# CanController.net
KiCad netlist of a schematic drawn in Altium Designer
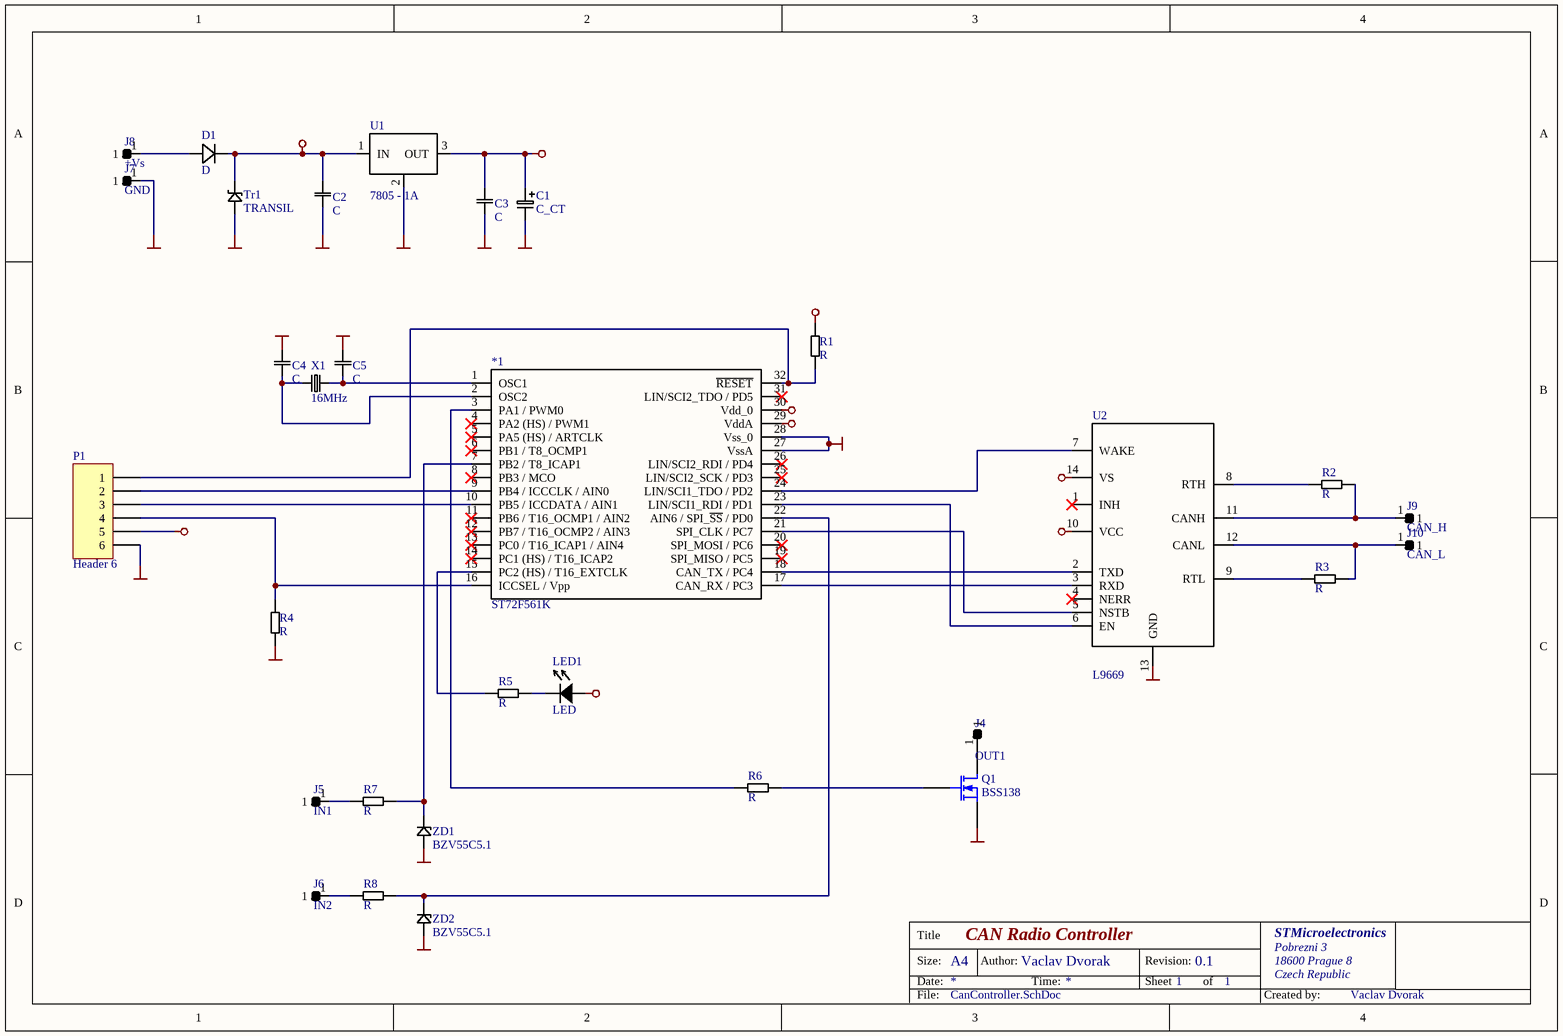
[diagram p0: CanController.SchDoc]

(export (version "E")
  (design (tool "Eeschema 10.0.6"))
  (components
    (comp (ref "*1")
      (value "ST72F561K")
      (footprint "QFP32")
      (libsource (lib "ABU_standard") (part "ST72F561K"))
    )
    (comp (ref "C1") (value "C_CT") (footprint "CTS A") (libsource (lib "ABU_standard") (part "C_CT")))
    (comp (ref "C2") (value "C") (footprint "C0805") (libsource (lib "ABU_standard") (part "C")))
    (comp (ref "C3") (value "C") (footprint "C0805") (libsource (lib "ABU_standard") (part "C")))
    (comp (ref "C4") (value "C") (footprint "C0805") (libsource (lib "ABU_standard") (part "C")))
    (comp (ref "C5") (value "C") (footprint "C0805") (libsource (lib "ABU_standard") (part "C")))
    (comp (ref "D1") (value "D") (footprint "SMA") (libsource (lib "ABU_STANDARD") (part "D")))
    (comp (ref "J4") (value "OUT1") (footprint "PIN") (libsource (lib "") (part "PIN_2")))
    (comp (ref "J5") (value "IN1") (footprint "PIN") (libsource (lib "ABU_standard") (part "PIN")))
    (comp (ref "J6") (value "IN2") (footprint "PIN") (libsource (lib "ABU_standard") (part "PIN")))
    (comp (ref "J7") (value "GND") (footprint "PIN") (libsource (lib "ABU_standard") (part "PIN")))
    (comp (ref "J8") (value "+Vs") (footprint "PIN") (libsource (lib "ABU_standard") (part "PIN")))
    (comp (ref "J9") (value "CAN_H") (footprint "PIN") (libsource (lib "") (part "PIN_1")))
    (comp (ref "J10") (value "CAN_L") (footprint "PIN") (libsource (lib "") (part "PIN_1")))
    (comp (ref "LED1") (value "LED") (footprint "LED_SMD") (libsource (lib "ABU_standard") (part "LED")))
    (comp (ref "P1")
      (value "Header 6")
      (footprint "HDR1X6")
      (description "Header, 6-Pin")
      (fields (field (name "PUBLISHER") "Altium Limited"))
      (libsource (lib "Miscellaneous Connectors") (part "Header 6"))
    )
    (comp (ref "Q1")
      (value "BSS138")
      (footprint "SOT23")
      (description "N-Channel Enhancement Mode Vertical DMOS FET")
      (fields (field (name "PUBLISHER") "Altium Limited"))
      (libsource (lib "ABU_standard") (part "BSS138"))
    )
    (comp (ref "R1") (value "R") (footprint "R0805") (libsource (lib "") (part "R_3")))
    (comp (ref "R2") (value "R") (footprint "R0805") (libsource (lib "") (part "R_2")))
    (comp (ref "R3") (value "R") (footprint "R0805") (libsource (lib "") (part "R_2")))
    (comp (ref "R4") (value "R") (footprint "R0805") (libsource (lib "") (part "R_1")))
    (comp (ref "R5") (value "R") (footprint "R0805") (libsource (lib "") (part "R_2")))
    (comp (ref "R6") (value "R") (footprint "R0805") (libsource (lib "ABU_standard") (part "R")))
    (comp (ref "R7") (value "R") (footprint "R0805") (libsource (lib "ABU_standard") (part "R")))
    (comp (ref "R8") (value "R") (footprint "R0805") (libsource (lib "ABU_standard") (part "R")))
    (comp (ref "Tr1") (value "TRANSIL") (footprint "SMAJ") (libsource (lib "ABU_STANDARD") (part "TRANSIL")))
    (comp (ref "U1")
      (value "7805 - 1A")
      (footprint "SOT-89")
      (libsource (lib "ABU_standard") (part "7805 - 1A"))
    )
    (comp (ref "U2")
      (value "L9669")
      (footprint "SO14")
      (libsource (lib "ABU_Door_module_project") (part "L9669"))
    )
    (comp (ref "X1") (value "16MHz") (footprint "HC-49U") (libsource (lib "ABU_standard") (part "XTALL")))
    (comp (ref "ZD1") (value "BZV55C5.1") (footprint "SOD80") (libsource (lib "ABU_standard") (part "ZD")))
    (comp (ref "ZD2") (value "BZV55C5.1") (footprint "SOD80") (libsource (lib "ABU_standard") (part "ZD")))
  )
  (nets
    (net (code "1") (name "+5V") (class "Default")
      (node (ref "*1") (pin "29") (pinfunction "VddA_29") (pintype "passive"))
      (node (ref "*1") (pin "30") (pinfunction "Vdd_0_30") (pintype "passive"))
      (node (ref "C1") (pin "1") (pinfunction "1_1") (pintype "passive"))
      (node (ref "C3") (pin "2") (pinfunction "2_2") (pintype "passive"))
      (node (ref "LED1") (pin "1") (pinfunction "A_1") (pintype "passive"))
      (node (ref "P1") (pin "5") (pinfunction "5_5") (pintype "passive"))
      (node (ref "R1") (pin "2") (pinfunction "2_2") (pintype "passive"))
      (node (ref "U1") (pin "3") (pinfunction "OUT_3") (pintype "passive"))
      (node (ref "U2") (pin "10") (pinfunction "VCC_10") (pintype "passive"))
    )
    (net (code "2") (name "GND") (class "Default")
      (node (ref "*1") (pin "27") (pinfunction "VssA_27") (pintype "passive"))
      (node (ref "*1") (pin "28") (pinfunction "Vss_0_28") (pintype "passive"))
      (node (ref "C1") (pin "2") (pinfunction "2_2") (pintype "passive"))
      (node (ref "C2") (pin "1") (pinfunction "1_1") (pintype "passive"))
      (node (ref "C3") (pin "1") (pinfunction "1_1") (pintype "passive"))
      (node (ref "C4") (pin "2") (pinfunction "2_2") (pintype "passive"))
      (node (ref "C5") (pin "2") (pinfunction "2_2") (pintype "passive"))
      (node (ref "J7") (pin "1") (pinfunction "1_1") (pintype "passive"))
      (node (ref "P1") (pin "6") (pinfunction "6_6") (pintype "passive"))
      (node (ref "Q1") (pin "2") (pinfunction "S_2") (pintype "passive"))
      (node (ref "R4") (pin "2") (pinfunction "2_2") (pintype "passive"))
      (node (ref "Tr1") (pin "1") (pinfunction "A_1") (pintype "passive"))
      (node (ref "U1") (pin "2") (pinfunction "Gnd_2") (pintype "passive"))
      (node (ref "U2") (pin "13") (pinfunction "GND_13") (pintype "passive"))
      (node (ref "ZD1") (pin "1") (pinfunction "A_1") (pintype "passive"))
      (node (ref "ZD2") (pin "1") (pinfunction "A_1") (pintype "passive"))
    )
    (net (code "3") (name "Net-(*1-AIN6_{slash}_SPI_~{SS}_{slash}_PD0)") (class "Default")
      (node (ref "*1") (pin "22") (pinfunction "AIN6_/_SPI_~{SS}_/_PD0_22") (pintype "passive"))
      (node (ref "R8") (pin "2") (pinfunction "2_2") (pintype "passive"))
      (node (ref "ZD2") (pin "2") (pinfunction "K_2") (pintype "passive"))
    )
    (net (code "4") (name "Net-(*1-CAN_RX_{slash}_PC3)") (class "Default")
      (node (ref "*1") (pin "17") (pinfunction "CAN_RX_/_PC3_17") (pintype "passive"))
      (node (ref "U2") (pin "3") (pinfunction "RXD_3") (pintype "passive"))
    )
    (net (code "5") (name "Net-(*1-CAN_TX_{slash}_PC4)") (class "Default")
      (node (ref "*1") (pin "18") (pinfunction "CAN_TX_/_PC4_18") (pintype "passive"))
      (node (ref "U2") (pin "2") (pinfunction "TXD_2") (pintype "passive"))
    )
    (net (code "6") (name "Net-(*1-ICCSEL_{slash}_Vpp)") (class "Default")
      (node (ref "*1") (pin "16") (pinfunction "ICCSEL_/_Vpp_16") (pintype "passive"))
      (node (ref "P1") (pin "4") (pinfunction "4_4") (pintype "passive"))
      (node (ref "R4") (pin "1") (pinfunction "1_1") (pintype "passive"))
    )
    (net (code "7") (name "Net-(*1-LIN{slash}SCI1_RDI_{slash}_PD1)") (class "Default")
      (node (ref "*1") (pin "23") (pinfunction "LIN/SCI1_RDI_/_PD1_23") (pintype "passive"))
      (node (ref "U2") (pin "6") (pinfunction "EN_6") (pintype "passive"))
    )
    (net (code "8") (name "Net-(*1-LIN{slash}SCI1_TDO_{slash}_PD2)") (class "Default")
      (node (ref "*1") (pin "24") (pinfunction "LIN/SCI1_TDO_/_PD2_24") (pintype "passive"))
      (node (ref "U2") (pin "7") (pinfunction "WAKE_7") (pintype "passive"))
    )
    (net (code "9") (name "Net-(*1-OSC1)") (class "Default")
      (node (ref "*1") (pin "1") (pinfunction "OSC1_1") (pintype "passive"))
      (node (ref "C5") (pin "1") (pinfunction "1_1") (pintype "passive"))
      (node (ref "X1") (pin "2") (pinfunction "2_2") (pintype "passive"))
    )
    (net (code "10") (name "Net-(*1-OSC2)") (class "Default")
      (node (ref "*1") (pin "2") (pinfunction "OSC2_2") (pintype "passive"))
      (node (ref "C4") (pin "1") (pinfunction "1_1") (pintype "passive"))
      (node (ref "X1") (pin "1") (pinfunction "1_1") (pintype "passive"))
    )
    (net (code "11") (name "Net-(*1-PA1_{slash}_PWM0)") (class "Default")
      (node (ref "*1") (pin "3") (pinfunction "PA1_/_PWM0_3") (pintype "passive"))
      (node (ref "R6") (pin "1") (pinfunction "1_1") (pintype "passive"))
    )
    (net (code "12") (name "Net-(*1-PB2_{slash}_T8_ICAP1)") (class "Default")
      (node (ref "*1") (pin "7") (pinfunction "PB2_/_T8_ICAP1_7") (pintype "passive"))
      (node (ref "R7") (pin "2") (pinfunction "2_2") (pintype "passive"))
      (node (ref "ZD1") (pin "2") (pinfunction "K_2") (pintype "passive"))
    )
    (net (code "13") (name "Net-(*1-PB4_{slash}_ICCCLK_{slash}_AIN0)") (class "Default")
      (node (ref "*1") (pin "9") (pinfunction "PB4_/_ICCCLK_/_AIN0_9") (pintype "passive"))
      (node (ref "P1") (pin "2") (pinfunction "2_2") (pintype "passive"))
    )
    (net (code "14") (name "Net-(*1-PB5_{slash}_ICCDATA_{slash}_AIN1)") (class "Default")
      (node (ref "*1") (pin "10") (pinfunction "PB5_/_ICCDATA_/_AIN1_10") (pintype "passive"))
      (node (ref "P1") (pin "3") (pinfunction "3_3") (pintype "passive"))
    )
    (net (code "15") (name "Net-(*1-PC2_(HS)_{slash}_T16_EXTCLK)") (class "Default")
      (node (ref "*1") (pin "15") (pinfunction "PC2_(HS)_/_T16_EXTCLK_15") (pintype "passive"))
      (node (ref "R5") (pin "2") (pinfunction "2_2") (pintype "passive"))
    )
    (net (code "16") (name "Net-(*1-SPI_CLK_{slash}_PC7)") (class "Default")
      (node (ref "*1") (pin "21") (pinfunction "SPI_CLK_/_PC7_21") (pintype "passive"))
      (node (ref "U2") (pin "5") (pinfunction "NSTB_5") (pintype "passive"))
    )
    (net (code "17") (name "Net-(*1-~{RESET})") (class "Default")
      (node (ref "*1") (pin "32") (pinfunction "~{RESET}_32") (pintype "passive"))
      (node (ref "P1") (pin "1") (pinfunction "1_1") (pintype "passive"))
      (node (ref "R1") (pin "1") (pinfunction "1_1") (pintype "passive"))
    )
    (net (code "18") (name "Net-(D1-A)") (class "Default")
      (node (ref "D1") (pin "1") (pinfunction "A_1") (pintype "passive"))
      (node (ref "J8") (pin "1") (pinfunction "1_1") (pintype "passive"))
    )
    (net (code "19") (name "Net-(J5-Pad1)") (class "Default")
      (node (ref "J5") (pin "1") (pinfunction "1_1") (pintype "passive"))
      (node (ref "R7") (pin "1") (pinfunction "1_1") (pintype "passive"))
    )
    (net (code "20") (name "Net-(J6-Pad1)") (class "Default")
      (node (ref "J6") (pin "1") (pinfunction "1_1") (pintype "passive"))
      (node (ref "R8") (pin "1") (pinfunction "1_1") (pintype "passive"))
    )
    (net (code "21") (name "Net-(LED1-K)") (class "Default")
      (node (ref "LED1") (pin "2") (pinfunction "K_2") (pintype "passive"))
      (node (ref "R5") (pin "1") (pinfunction "1_1") (pintype "passive"))
    )
    (net (code "22") (name "Net-(Q1-D)") (class "Default")
      (node (ref "J4") (pin "1") (pinfunction "1_1") (pintype "passive"))
      (node (ref "Q1") (pin "3") (pinfunction "D_3") (pintype "passive"))
    )
    (net (code "23") (name "Net-(Q1-G)") (class "Default")
      (node (ref "Q1") (pin "1") (pinfunction "G_1") (pintype "passive"))
      (node (ref "R6") (pin "2") (pinfunction "2_2") (pintype "passive"))
    )
    (net (code "24") (name "Net-(U2-CANH)") (class "Default")
      (node (ref "J9") (pin "1") (pinfunction "1_1") (pintype "passive"))
      (node (ref "R2") (pin "1") (pinfunction "1_1") (pintype "passive"))
      (node (ref "U2") (pin "11") (pinfunction "CANH_11") (pintype "passive"))
    )
    (net (code "25") (name "Net-(U2-CANL)") (class "Default")
      (node (ref "J10") (pin "1") (pinfunction "1_1") (pintype "passive"))
      (node (ref "R3") (pin "1") (pinfunction "1_1") (pintype "passive"))
      (node (ref "U2") (pin "12") (pinfunction "CANL_12") (pintype "passive"))
    )
    (net (code "26") (name "Net-(U2-RTH)") (class "Default")
      (node (ref "R2") (pin "2") (pinfunction "2_2") (pintype "passive"))
      (node (ref "U2") (pin "8") (pinfunction "RTH_8") (pintype "passive"))
    )
    (net (code "27") (name "Net-(U2-RTL)") (class "Default")
      (node (ref "R3") (pin "2") (pinfunction "2_2") (pintype "passive"))
      (node (ref "U2") (pin "9") (pinfunction "RTL_9") (pintype "passive"))
    )
    (net (code "28") (name "Vs") (class "Default")
      (node (ref "C2") (pin "2") (pinfunction "2_2") (pintype "passive"))
      (node (ref "D1") (pin "2") (pinfunction "K_2") (pintype "passive"))
      (node (ref "Tr1") (pin "2") (pinfunction "K_2") (pintype "passive"))
      (node (ref "U1") (pin "1") (pinfunction "IN_1") (pintype "passive"))
      (node (ref "U2") (pin "14") (pinfunction "VS_14") (pintype "passive"))
    )
    (net (code "29") (name "unconnected-(*1-LIN{slash}SCI2_RDI_{slash}_PD4-Pad26)") (class "Default")
      (node (ref "*1") (pin "26") (pinfunction "LIN/SCI2_RDI_/_PD4_26") (pintype "passive+no_connect"))
    )
    (net (code "30") (name "unconnected-(*1-LIN{slash}SCI2_SCK_{slash}_PD3-Pad25)") (class "Default")
      (node (ref "*1") (pin "25") (pinfunction "LIN/SCI2_SCK_/_PD3_25") (pintype "passive+no_connect"))
    )
    (net (code "31") (name "unconnected-(*1-LIN{slash}SCI2_TDO_{slash}_PD5-Pad31)") (class "Default")
      (node (ref "*1") (pin "31") (pinfunction "LIN/SCI2_TDO_/_PD5_31") (pintype "passive+no_connect"))
    )
    (net (code "32") (name "unconnected-(*1-PA2_(HS)_{slash}_PWM1-Pad4)") (class "Default")
      (node (ref "*1") (pin "4") (pinfunction "PA2_(HS)_/_PWM1_4") (pintype "passive+no_connect"))
    )
    (net (code "33") (name "unconnected-(*1-PA5_(HS)_{slash}_ARTCLK-Pad5)") (class "Default")
      (node (ref "*1") (pin "5") (pinfunction "PA5_(HS)_/_ARTCLK_5") (pintype "passive+no_connect"))
    )
    (net (code "34") (name "unconnected-(*1-PB1_{slash}_T8_OCMP1-Pad6)") (class "Default")
      (node (ref "*1") (pin "6") (pinfunction "PB1_/_T8_OCMP1_6") (pintype "passive+no_connect"))
    )
    (net (code "35") (name "unconnected-(*1-PB3_{slash}_MCO-Pad8)") (class "Default")
      (node (ref "*1") (pin "8") (pinfunction "PB3_/_MCO_8") (pintype "passive+no_connect"))
    )
    (net (code "36") (name "unconnected-(*1-PB6_{slash}_T16_OCMP1_{slash}_AIN2-Pad11)") (class "Default")
      (node (ref "*1") (pin "11") (pinfunction "PB6_/_T16_OCMP1_/_AIN2_11") (pintype "passive+no_connect"))
    )
    (net (code "37") (name "unconnected-(*1-PB7_{slash}_T16_OCMP2_{slash}_AIN3-Pad12)") (class "Default")
      (node (ref "*1") (pin "12") (pinfunction "PB7_/_T16_OCMP2_/_AIN3_12") (pintype "passive+no_connect"))
    )
    (net (code "38") (name "unconnected-(*1-PC0_{slash}_T16_ICAP1_{slash}_AIN4-Pad13)") (class "Default")
      (node (ref "*1") (pin "13") (pinfunction "PC0_/_T16_ICAP1_/_AIN4_13") (pintype "passive+no_connect"))
    )
    (net (code "39") (name "unconnected-(*1-PC1_(HS)_{slash}_T16_ICAP2-Pad14)") (class "Default")
      (node (ref "*1") (pin "14") (pinfunction "PC1_(HS)_/_T16_ICAP2_14") (pintype "passive+no_connect"))
    )
    (net (code "40") (name "unconnected-(*1-SPI_MISO_{slash}_PC5-Pad19)") (class "Default")
      (node (ref "*1") (pin "19") (pinfunction "SPI_MISO_/_PC5_19") (pintype "passive+no_connect"))
    )
    (net (code "41") (name "unconnected-(*1-SPI_MOSI_{slash}_PC6-Pad20)") (class "Default")
      (node (ref "*1") (pin "20") (pinfunction "SPI_MOSI_/_PC6_20") (pintype "passive+no_connect"))
    )
    (net (code "42") (name "unconnected-(U2-INH-Pad1)") (class "Default")
      (node (ref "U2") (pin "1") (pinfunction "INH_1") (pintype "passive+no_connect"))
    )
    (net (code "43") (name "unconnected-(U2-NERR-Pad4)") (class "Default")
      (node (ref "U2") (pin "4") (pinfunction "NERR_4") (pintype "passive+no_connect"))
    )
  )
)
